# OpenEVSE_PLUS_v2.net
KiCad netlist of a schematic drawn in EAGLE
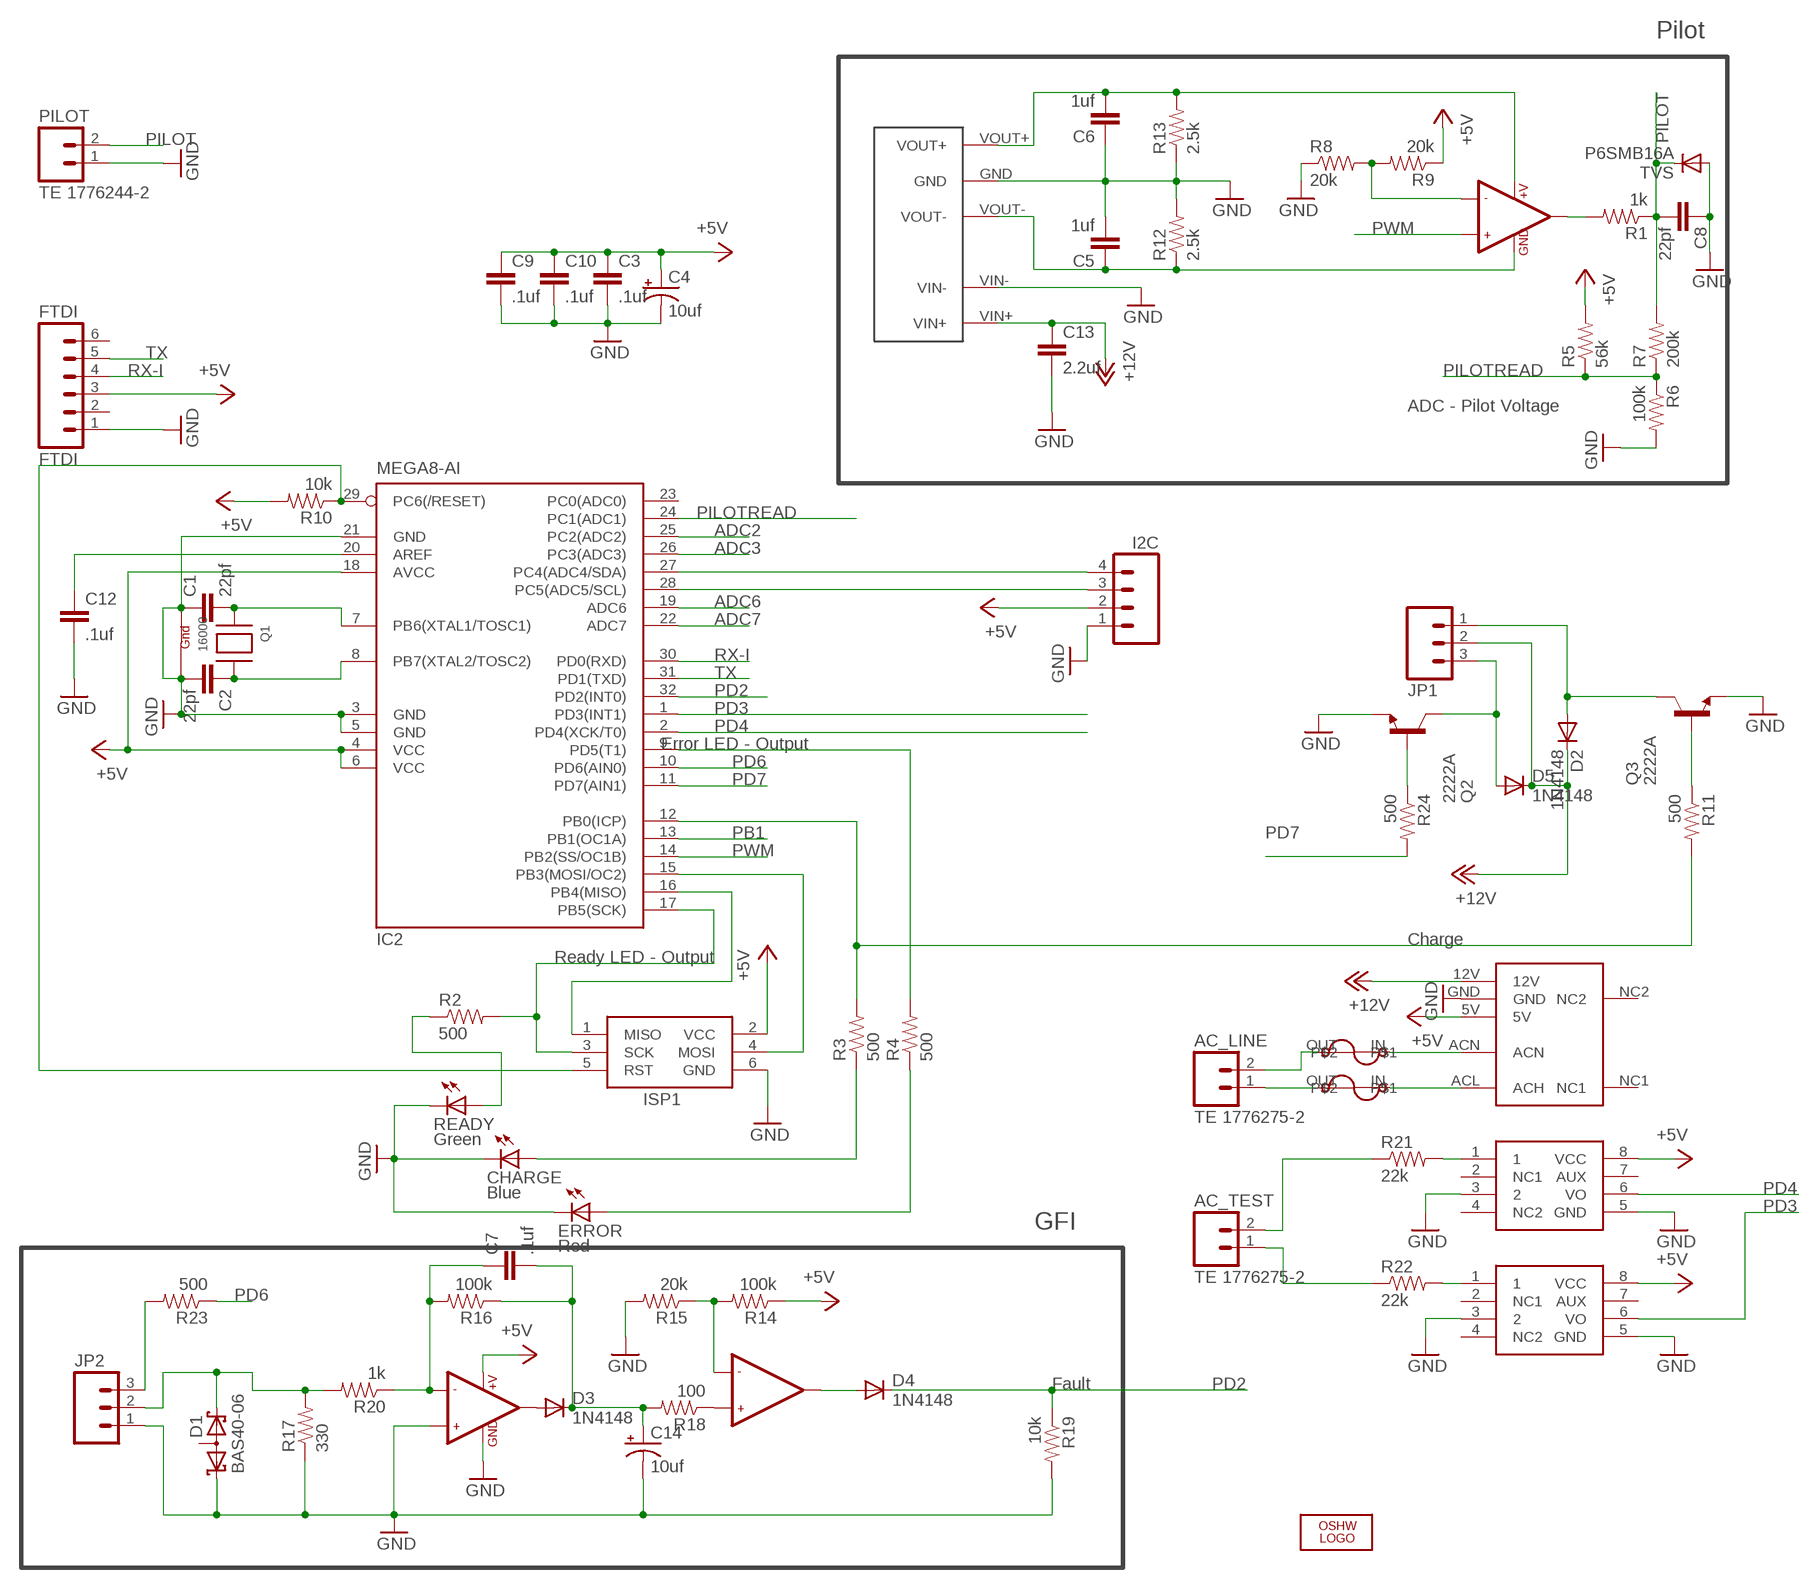
[diagram p0: schematic, sheet 1]

(export (version "E")
  (design (tool "Eeschema 10.0.6"))
  (components
    (comp (ref "AC_LINE")
      (value "TE 1776275-2")
      (footprint "eagle-import:SCREWTERMINAL-3.5MM-2_LOCK")
      (libsource (lib "eagle-import") (part "M023.5MM_LOCK"))
    )
    (comp (ref "AC_TEST")
      (value "TE 1776275-2")
      (footprint "eagle-import:SCREWTERMINAL-3.5MM-2_LOCK")
      (libsource (lib "eagle-import") (part "M023.5MM_LOCK"))
    )
    (comp (ref "C1")
      (value "22pf")
      (footprint "eagle-import:0805")
      (libsource (lib "eagle-import") (part "CAP0805"))
    )
    (comp (ref "C2")
      (value "22pf")
      (footprint "eagle-import:0805")
      (libsource (lib "eagle-import") (part "CAP0805"))
    )
    (comp (ref "C3")
      (value ".1uf")
      (footprint "eagle-import:0805")
      (libsource (lib "eagle-import") (part "CAP0805"))
    )
    (comp (ref "C4")
      (value "10uf")
      (footprint "eagle-import:EIA3216")
      (libsource (lib "eagle-import") (part "CAP_POL1206"))
    )
    (comp (ref "C5")
      (value "1uf")
      (footprint "eagle-import:0805")
      (libsource (lib "eagle-import") (part "CAP0805"))
    )
    (comp (ref "C6")
      (value "1uf")
      (footprint "eagle-import:0805")
      (libsource (lib "eagle-import") (part "CAP0805"))
    )
    (comp (ref "C7")
      (value ".1uf")
      (footprint "eagle-import:0805")
      (libsource (lib "eagle-import") (part "CAP0805"))
    )
    (comp (ref "C8")
      (value "22pf")
      (footprint "eagle-import:0805")
      (libsource (lib "eagle-import") (part "CAP0805"))
    )
    (comp (ref "C9")
      (value ".1uf")
      (footprint "eagle-import:0805")
      (libsource (lib "eagle-import") (part "CAP0805"))
    )
    (comp (ref "C10")
      (value ".1uf")
      (footprint "eagle-import:0805")
      (libsource (lib "eagle-import") (part "CAP0805"))
    )
    (comp (ref "C12")
      (value ".1uf")
      (footprint "eagle-import:0805")
      (libsource (lib "eagle-import") (part "CAP0805"))
    )
    (comp (ref "C13")
      (value "2.2uf")
      (footprint "eagle-import:0805")
      (libsource (lib "eagle-import") (part "CAP0805"))
    )
    (comp (ref "C14")
      (value "10uf")
      (footprint "eagle-import:EIA3216")
      (libsource (lib "eagle-import") (part "CAP_POL1206"))
    )
    (comp (ref "CHARGE")
      (value "Blue")
      (footprint "eagle-import:LED-0603")
      (libsource (lib "eagle-import") (part "LED0603"))
    )
    (comp (ref "D1")
      (value "BAS40-06")
      (footprint "eagle-import:SOT23")
      (libsource (lib "eagle-import") (part "BAS40-06"))
    )
    (comp (ref "D2")
      (value "1N4148")
      (footprint "eagle-import:SOD123")
      (libsource (lib "eagle-import") (part "DIODE-SOD123"))
    )
    (comp (ref "D3")
      (value "1N4148")
      (footprint "eagle-import:SOD123")
      (libsource (lib "eagle-import") (part "DIODE-SOD123"))
    )
    (comp (ref "D4")
      (value "1N4148")
      (footprint "eagle-import:SOD123")
      (libsource (lib "eagle-import") (part "DIODE-SOD123"))
    )
    (comp (ref "D5")
      (value "1N4148")
      (footprint "eagle-import:SOD123")
      (libsource (lib "eagle-import") (part "DIODE-SOD123"))
    )
    (comp (ref "DCDC")
      (value "D107E")
      (footprint "eagle-import:DCDC_SIP")
      (libsource (lib "eagle-import") (part "DCDC_SIP"))
    )
    (comp (ref "ERROR")
      (value "Red")
      (footprint "eagle-import:LED-0603")
      (libsource (lib "eagle-import") (part "LED0603"))
    )
    (comp (ref "FTDI")
      (value "FTDI")
      (footprint "eagle-import:1X06_LOCK")
      (libsource (lib "eagle-import") (part "M06LOCK"))
    )
    (comp (ref "I2C")
      (value "M04LOCK")
      (footprint "eagle-import:1X04_LOCK")
      (libsource (lib "eagle-import") (part "M04LOCK"))
    )
    (comp (ref "IC1")
      (value "MID400")
      (footprint "eagle-import:DIP08")
      (libsource (lib "eagle-import") (part "MID400"))
    )
    (comp (ref "IC2")
      (value "MEGA8-AI")
      (footprint "eagle-import:TQFP32-08")
      (fields (field (name "MPN") "ATMEGA8-16AU"))
      (libsource (lib "eagle-import") (part "MEGA8-AI"))
    )
    (comp (ref "IC3")
      (value "LMV358")
      (footprint "eagle-import:SO08")
      (libsource (lib "eagle-import") (part "LMV358"))
    )
    (comp (ref "IC4")
      (value "LMV358")
      (footprint "eagle-import:SO08")
      (libsource (lib "eagle-import") (part "LMV358"))
    )
    (comp (ref "IC5")
      (value "MID400")
      (footprint "eagle-import:DIP08")
      (libsource (lib "eagle-import") (part "MID400"))
    )
    (comp (ref "ISP1")
      (value "AVRISP-6")
      (footprint "eagle-import:AVRISP")
      (libsource (lib "eagle-import") (part "AVRISP-6"))
    )
    (comp (ref "JP1")
      (value "M03SCREW_LOCK")
      (footprint "eagle-import:SCREWTERMINAL-3.5MM-3_LOCK.007S")
      (libsource (lib "eagle-import") (part "M03SCREW_LOCK"))
    )
    (comp (ref "JP2")
      (value "M03LOCK")
      (footprint "eagle-import:1X03_LOCK")
      (libsource (lib "eagle-import") (part "M03LOCK"))
    )
    (comp (ref "LOGO1")
      (value "OSHW_LOGO_8MILX0150-NT")
      (footprint "eagle-import:OSHW_8X150_NOTEXT")
      (libsource (lib "eagle-import") (part "OSHW_LOGO_8MILX0150-NT"))
    )
    (comp (ref "PILOT")
      (value "TE 1776244-2")
      (footprint "eagle-import:SCREWTERMINAL-5MM-2")
      (libsource (lib "eagle-import") (part "M025MM"))
    )
    (comp (ref "Q1")
      (value "16000")
      (footprint "eagle-import:NX3225")
      (libsource (lib "eagle-import") (part "XTAL-4-3225"))
    )
    (comp (ref "Q2")
      (value "2222A")
      (footprint "eagle-import:SOT23")
      (libsource (lib "eagle-import") (part "BCX70SMD"))
    )
    (comp (ref "Q3")
      (value "2222A")
      (footprint "eagle-import:SOT23")
      (libsource (lib "eagle-import") (part "BCX70SMD"))
    )
    (comp (ref "R1")
      (value "1k")
      (footprint "eagle-import:0805")
      (libsource (lib "eagle-import") (part "RESISTOR0805-RES"))
    )
    (comp (ref "R2")
      (value "500")
      (footprint "eagle-import:0805")
      (libsource (lib "eagle-import") (part "RESISTOR0805-RES"))
    )
    (comp (ref "R3")
      (value "500")
      (footprint "eagle-import:0805")
      (libsource (lib "eagle-import") (part "RESISTOR0805-RES"))
    )
    (comp (ref "R4")
      (value "500")
      (footprint "eagle-import:0805")
      (libsource (lib "eagle-import") (part "RESISTOR0805-RES"))
    )
    (comp (ref "R5")
      (value "56k")
      (footprint "eagle-import:0805")
      (libsource (lib "eagle-import") (part "RESISTOR0805-RES"))
    )
    (comp (ref "R6")
      (value "100k")
      (footprint "eagle-import:0805")
      (libsource (lib "eagle-import") (part "RESISTOR0805-RES"))
    )
    (comp (ref "R7")
      (value "200k")
      (footprint "eagle-import:0805")
      (libsource (lib "eagle-import") (part "RESISTOR0805-RES"))
    )
    (comp (ref "R8")
      (value "20k")
      (footprint "eagle-import:0805")
      (libsource (lib "eagle-import") (part "RESISTOR0805-RES"))
    )
    (comp (ref "R9")
      (value "20k")
      (footprint "eagle-import:0805")
      (libsource (lib "eagle-import") (part "RESISTOR0805-RES"))
    )
    (comp (ref "R10")
      (value "10k")
      (footprint "eagle-import:0805")
      (libsource (lib "eagle-import") (part "RESISTOR0805-RES"))
    )
    (comp (ref "R11")
      (value "500")
      (footprint "eagle-import:0805")
      (libsource (lib "eagle-import") (part "RESISTOR0805-RES"))
    )
    (comp (ref "R12")
      (value "2.5k")
      (footprint "eagle-import:0805")
      (libsource (lib "eagle-import") (part "RESISTOR0805-RES"))
    )
    (comp (ref "R13")
      (value "2.5k")
      (footprint "eagle-import:0805")
      (libsource (lib "eagle-import") (part "RESISTOR0805-RES"))
    )
    (comp (ref "R14")
      (value "100k")
      (footprint "eagle-import:0805")
      (libsource (lib "eagle-import") (part "RESISTOR0805-RES"))
    )
    (comp (ref "R15")
      (value "20k")
      (footprint "eagle-import:0805")
      (libsource (lib "eagle-import") (part "RESISTOR0805-RES"))
    )
    (comp (ref "R16")
      (value "100k")
      (footprint "eagle-import:0805")
      (libsource (lib "eagle-import") (part "RESISTOR0805-RES"))
    )
    (comp (ref "R17")
      (value "330")
      (footprint "eagle-import:0805")
      (libsource (lib "eagle-import") (part "RESISTOR0805-RES"))
    )
    (comp (ref "R18")
      (value "100")
      (footprint "eagle-import:0805")
      (libsource (lib "eagle-import") (part "RESISTOR0805-RES"))
    )
    (comp (ref "R19")
      (value "10k")
      (footprint "eagle-import:0805")
      (libsource (lib "eagle-import") (part "RESISTOR0805-RES"))
    )
    (comp (ref "R20")
      (value "1k")
      (footprint "eagle-import:0805")
      (libsource (lib "eagle-import") (part "RESISTOR0805-RES"))
    )
    (comp (ref "R21")
      (value "22k")
      (footprint "eagle-import:AXIAL-0.4")
      (libsource (lib "eagle-import") (part "RESISTORPTH-1/4W"))
    )
    (comp (ref "R22")
      (value "22k")
      (footprint "eagle-import:AXIAL-0.4")
      (libsource (lib "eagle-import") (part "RESISTORPTH-1/4W"))
    )
    (comp (ref "R23")
      (value "500")
      (footprint "eagle-import:0805")
      (libsource (lib "eagle-import") (part "RESISTOR0805-RES"))
    )
    (comp (ref "R24")
      (value "500")
      (footprint "eagle-import:0805")
      (libsource (lib "eagle-import") (part "RESISTOR0805-RES"))
    )
    (comp (ref "READY")
      (value "Green")
      (footprint "eagle-import:LED-0603")
      (libsource (lib "eagle-import") (part "LED0603"))
    )
    (comp (ref "TVS")
      (value "P6SMB16A")
      (footprint "eagle-import:SMB")
      (libsource (lib "eagle-import") (part "DIODE-SMB"))
    )
    (comp (ref "U$1")
      (value "MPM-04E-1205")
      (footprint "eagle-import:MPM-04E-1205")
      (libsource (lib "eagle-import") (part "MPM-04E-1205"))
    )
    (comp (ref "U$2")
      (value "BEL1AFUSE")
      (footprint "eagle-import:BELFUSE1A")
      (libsource (lib "eagle-import") (part "BEL1AFUSE"))
    )
    (comp (ref "U$5")
      (value "BEL1AFUSE")
      (footprint "eagle-import:BELFUSE1A")
      (libsource (lib "eagle-import") (part "BEL1AFUSE"))
    )
  )
  (nets
    (net (code "1") (name "+5V") (class "Default")
      (node (ref "C10") (pin "1") (pinfunction "1_1") (pintype "passive"))
      (node (ref "C3") (pin "1") (pinfunction "1_1") (pintype "passive"))
      (node (ref "C4") (pin "A") (pinfunction "+_A") (pintype "passive"))
      (node (ref "C9") (pin "1") (pinfunction "1_1") (pintype "passive"))
      (node (ref "FTDI") (pin "3") (pinfunction "3_3") (pintype "passive"))
      (node (ref "I2C") (pin "2") (pinfunction "2_2") (pintype "passive"))
      (node (ref "IC1") (pin "8") (pinfunction "VCC_8") (pintype "bidirectional"))
      (node (ref "IC2") (pin "18") (pinfunction "AVCC_18") (pintype "power_in"))
      (node (ref "IC2") (pin "4") (pinfunction "VCC_4") (pintype "power_in"))
      (node (ref "IC2") (pin "6") (pinfunction "VCC_6") (pintype "power_in"))
      (node (ref "IC3") (pin "8") (pinfunction "+V_8") (pintype "power_in"))
      (node (ref "IC5") (pin "8") (pinfunction "VCC_8") (pintype "bidirectional"))
      (node (ref "ISP1") (pin "2") (pinfunction "VCC_2") (pintype "power_in"))
      (node (ref "R10") (pin "2") (pinfunction "2_2") (pintype "passive"))
      (node (ref "R14") (pin "1") (pinfunction "1_1") (pintype "passive"))
      (node (ref "R5") (pin "2") (pinfunction "2_2") (pintype "passive"))
      (node (ref "R9") (pin "1") (pinfunction "1_1") (pintype "passive"))
      (node (ref "U$1") (pin "5V") (pinfunction "5V_5V") (pintype "bidirectional"))
    )
    (net (code "2") (name "+12V") (class "Default")
      (node (ref "C13") (pin "1") (pinfunction "1_1") (pintype "passive"))
      (node (ref "D2") (pin "C") (pinfunction "C_C") (pintype "passive"))
      (node (ref "D5") (pin "C") (pinfunction "C_C") (pintype "passive"))
      (node (ref "DCDC") (pin "VIN+") (pinfunction "VIN+_VIN+") (pintype "bidirectional"))
      (node (ref "JP1") (pin "2") (pinfunction "2_2") (pintype "passive"))
      (node (ref "U$1") (pin "12V") (pinfunction "12V_12V") (pintype "bidirectional"))
    )
    (net (code "3") (name "/ADC2") (class "Default")
      (node (ref "IC2") (pin "25") (pinfunction "PC2(ADC2)_25") (pintype "bidirectional"))
    )
    (net (code "4") (name "/ADC3") (class "Default")
      (node (ref "IC2") (pin "26") (pinfunction "PC3(ADC3)_26") (pintype "bidirectional"))
    )
    (net (code "5") (name "/ADC6") (class "Default")
      (node (ref "IC2") (pin "19") (pinfunction "ADC6_19") (pintype "bidirectional"))
    )
    (net (code "6") (name "/ADC7") (class "Default")
      (node (ref "IC2") (pin "22") (pinfunction "ADC7_22") (pintype "bidirectional"))
    )
    (net (code "7") (name "/PB1") (class "Default")
      (node (ref "IC2") (pin "13") (pinfunction "PB1(OC1A)_13") (pintype "bidirectional"))
    )
    (net (code "8") (name "/PD2") (class "Default")
      (node (ref "D4") (pin "C") (pinfunction "C_C") (pintype "passive"))
      (node (ref "IC2") (pin "32") (pinfunction "PD2(INT0)_32") (pintype "bidirectional"))
      (node (ref "R19") (pin "1") (pinfunction "1_1") (pintype "passive"))
    )
    (net (code "9") (name "/PD3") (class "Default")
      (node (ref "IC2") (pin "1") (pinfunction "PD3(INT1)_1") (pintype "bidirectional"))
      (node (ref "IC5") (pin "6") (pinfunction "VO_6") (pintype "bidirectional"))
    )
    (net (code "10") (name "/PD4") (class "Default")
      (node (ref "IC1") (pin "6") (pinfunction "VO_6") (pintype "bidirectional"))
      (node (ref "IC2") (pin "2") (pinfunction "PD4(XCK/T0)_2") (pintype "bidirectional"))
    )
    (net (code "11") (name "/PD6") (class "Default")
      (node (ref "IC2") (pin "10") (pinfunction "PD6(AIN0)_10") (pintype "bidirectional"))
      (node (ref "R23") (pin "1") (pinfunction "1_1") (pintype "passive"))
    )
    (net (code "12") (name "/PD7") (class "Default")
      (node (ref "IC2") (pin "11") (pinfunction "PD7(AIN1)_11") (pintype "bidirectional"))
      (node (ref "R24") (pin "2") (pinfunction "2_2") (pintype "passive"))
    )
    (net (code "13") (name "/PILOT") (class "Default")
      (node (ref "C8") (pin "2") (pinfunction "2_2") (pintype "passive"))
      (node (ref "PILOT") (pin "2") (pinfunction "2_2") (pintype "passive"))
      (node (ref "R1") (pin "1") (pinfunction "1_1") (pintype "passive"))
      (node (ref "R7") (pin "2") (pinfunction "2_2") (pintype "passive"))
      (node (ref "TVS") (pin "C") (pinfunction "C_C") (pintype "passive"))
    )
    (net (code "14") (name "/PILOTREAD") (class "Default")
      (node (ref "IC2") (pin "24") (pinfunction "PC1(ADC1)_24") (pintype "bidirectional"))
      (node (ref "R5") (pin "1") (pinfunction "1_1") (pintype "passive"))
      (node (ref "R6") (pin "1") (pinfunction "1_1") (pintype "passive"))
      (node (ref "R7") (pin "1") (pinfunction "1_1") (pintype "passive"))
    )
    (net (code "15") (name "/PWM") (class "Default")
      (node (ref "IC2") (pin "14") (pinfunction "PB2(SS/OC1B)_14") (pintype "bidirectional"))
      (node (ref "IC4") (pin "3") (pinfunction "+IN1_3") (pintype "input"))
    )
    (net (code "16") (name "/RX-I") (class "Default")
      (node (ref "FTDI") (pin "4") (pinfunction "4_4") (pintype "passive"))
      (node (ref "IC2") (pin "30") (pinfunction "PD0(RXD)_30") (pintype "bidirectional"))
    )
    (net (code "17") (name "/TX") (class "Default")
      (node (ref "FTDI") (pin "5") (pinfunction "5_5") (pintype "passive"))
      (node (ref "IC2") (pin "31") (pinfunction "PD1(TXD)_31") (pintype "bidirectional"))
    )
    (net (code "18") (name "GND") (class "Default")
      (node (ref "C1") (pin "1") (pinfunction "1_1") (pintype "passive"))
      (node (ref "C10") (pin "2") (pinfunction "2_2") (pintype "passive"))
      (node (ref "C12") (pin "2") (pinfunction "2_2") (pintype "passive"))
      (node (ref "C13") (pin "2") (pinfunction "2_2") (pintype "passive"))
      (node (ref "C14") (pin "C") (pinfunction "-_C") (pintype "passive"))
      (node (ref "C2") (pin "2") (pinfunction "2_2") (pintype "passive"))
      (node (ref "C3") (pin "2") (pinfunction "2_2") (pintype "passive"))
      (node (ref "C4") (pin "C") (pinfunction "-_C") (pintype "passive"))
      (node (ref "C5") (pin "2") (pinfunction "2_2") (pintype "passive"))
      (node (ref "C6") (pin "1") (pinfunction "1_1") (pintype "passive"))
      (node (ref "C8") (pin "1") (pinfunction "1_1") (pintype "passive"))
      (node (ref "C9") (pin "2") (pinfunction "2_2") (pintype "passive"))
      (node (ref "CHARGE") (pin "C") (pinfunction "C_C") (pintype "passive"))
      (node (ref "D1") (pin "1") (pinfunction "K1_1") (pintype "passive"))
      (node (ref "DCDC") (pin "GND") (pinfunction "GND_GND") (pintype "bidirectional"))
      (node (ref "DCDC") (pin "VIN-") (pinfunction "VIN-_VIN-") (pintype "bidirectional"))
      (node (ref "ERROR") (pin "C") (pinfunction "C_C") (pintype "passive"))
      (node (ref "FTDI") (pin "1") (pinfunction "1_1") (pintype "passive"))
      (node (ref "I2C") (pin "1") (pinfunction "1_1") (pintype "passive"))
      (node (ref "IC1") (pin "3") (pinfunction "2_3") (pintype "bidirectional"))
      (node (ref "IC1") (pin "5") (pinfunction "GND_5") (pintype "bidirectional"))
      (node (ref "IC2") (pin "21") (pinfunction "GND_21") (pintype "power_in"))
      (node (ref "IC2") (pin "3") (pinfunction "GND_3") (pintype "power_in"))
      (node (ref "IC2") (pin "5") (pinfunction "GND_5") (pintype "power_in"))
      (node (ref "IC3") (pin "3") (pinfunction "+IN1_3") (pintype "input"))
      (node (ref "IC3") (pin "4") (pinfunction "GND_4") (pintype "power_in"))
      (node (ref "IC5") (pin "3") (pinfunction "2_3") (pintype "bidirectional"))
      (node (ref "IC5") (pin "5") (pinfunction "GND_5") (pintype "bidirectional"))
      (node (ref "ISP1") (pin "6") (pinfunction "GND_6") (pintype "power_in"))
      (node (ref "JP2") (pin "1") (pinfunction "1_1") (pintype "passive"))
      (node (ref "PILOT") (pin "1") (pinfunction "1_1") (pintype "passive"))
      (node (ref "Q1") (pin "1") (pinfunction "G1_1") (pintype "power_in"))
      (node (ref "Q1") (pin "3") (pinfunction "G2_3") (pintype "power_in"))
      (node (ref "Q2") (pin "2") (pinfunction "E_2") (pintype "passive"))
      (node (ref "Q3") (pin "2") (pinfunction "E_2") (pintype "passive"))
      (node (ref "R12") (pin "2") (pinfunction "2_2") (pintype "passive"))
      (node (ref "R13") (pin "1") (pinfunction "1_1") (pintype "passive"))
      (node (ref "R15") (pin "2") (pinfunction "2_2") (pintype "passive"))
      (node (ref "R17") (pin "1") (pinfunction "1_1") (pintype "passive"))
      (node (ref "R19") (pin "2") (pinfunction "2_2") (pintype "passive"))
      (node (ref "R6") (pin "2") (pinfunction "2_2") (pintype "passive"))
      (node (ref "R8") (pin "1") (pinfunction "1_1") (pintype "passive"))
      (node (ref "READY") (pin "C") (pinfunction "C_C") (pintype "passive"))
      (node (ref "TVS") (pin "A") (pinfunction "A_A") (pintype "passive"))
      (node (ref "U$1") (pin "GND") (pinfunction "GND_GND") (pintype "bidirectional"))
    )
    (net (code "19") (name "Net-(C14-+)") (class "Default")
      (node (ref "C14") (pin "A") (pinfunction "+_A") (pintype "passive"))
      (node (ref "C7") (pin "2") (pinfunction "2_2") (pintype "passive"))
      (node (ref "D3") (pin "C") (pinfunction "C_C") (pintype "passive"))
      (node (ref "R16") (pin "1") (pinfunction "1_1") (pintype "passive"))
      (node (ref "R18") (pin "2") (pinfunction "2_2") (pintype "passive"))
    )
    (net (code "20") (name "Net-(CHARGE-PadA)") (class "Default")
      (node (ref "CHARGE") (pin "A") (pinfunction "A_A") (pintype "passive"))
      (node (ref "R3") (pin "1") (pinfunction "1_1") (pintype "passive"))
    )
    (net (code "21") (name "Net-(D1-K2)") (class "Default")
      (node (ref "D1") (pin "2") (pinfunction "K2_2") (pintype "passive"))
      (node (ref "JP2") (pin "2") (pinfunction "2_2") (pintype "passive"))
      (node (ref "R17") (pin "2") (pinfunction "2_2") (pintype "passive"))
      (node (ref "R20") (pin "2") (pinfunction "2_2") (pintype "passive"))
    )
    (net (code "22") (name "Net-(ERROR-PadA)") (class "Default")
      (node (ref "ERROR") (pin "A") (pinfunction "A_A") (pintype "passive"))
      (node (ref "R4") (pin "1") (pinfunction "1_1") (pintype "passive"))
    )
    (net (code "23") (name "Net-(IC2-AREF)") (class "Default")
      (node (ref "C12") (pin "1") (pinfunction "1_1") (pintype "passive"))
      (node (ref "IC2") (pin "20") (pinfunction "AREF_20") (pintype "passive"))
    )
    (net (code "24") (name "Net-(IC2-PB0(ICP))") (class "Default")
      (node (ref "IC2") (pin "12") (pinfunction "PB0(ICP)_12") (pintype "bidirectional"))
      (node (ref "R11") (pin "2") (pinfunction "2_2") (pintype "passive"))
      (node (ref "R3") (pin "2") (pinfunction "2_2") (pintype "passive"))
    )
    (net (code "25") (name "Net-(IC2-PB3(MOSI{slash}OC2))") (class "Default")
      (node (ref "IC2") (pin "15") (pinfunction "PB3(MOSI/OC2)_15") (pintype "bidirectional"))
      (node (ref "ISP1") (pin "4") (pinfunction "MOSI_4") (pintype "output"))
    )
    (net (code "26") (name "Net-(IC2-PB4(MISO))") (class "Default")
      (node (ref "IC2") (pin "16") (pinfunction "PB4(MISO)_16") (pintype "bidirectional"))
      (node (ref "ISP1") (pin "1") (pinfunction "MISO_1") (pintype "input"))
    )
    (net (code "27") (name "Net-(IC2-PB5(SCK))") (class "Default")
      (node (ref "IC2") (pin "17") (pinfunction "PB5(SCK)_17") (pintype "bidirectional"))
      (node (ref "ISP1") (pin "3") (pinfunction "SCK_3") (pintype "output"))
      (node (ref "R2") (pin "2") (pinfunction "2_2") (pintype "passive"))
    )
    (net (code "28") (name "Net-(IC2-PB6(XTAL1{slash}TOSC1))") (class "Default")
      (node (ref "C1") (pin "2") (pinfunction "2_2") (pintype "passive"))
      (node (ref "IC2") (pin "7") (pinfunction "PB6(XTAL1/TOSC1)_7") (pintype "bidirectional"))
      (node (ref "Q1") (pin "2") (pinfunction "X1_2") (pintype "bidirectional"))
    )
    (net (code "29") (name "Net-(IC2-PB7(XTAL2{slash}TOSC2))") (class "Default")
      (node (ref "C2") (pin "1") (pinfunction "1_1") (pintype "passive"))
      (node (ref "IC2") (pin "8") (pinfunction "PB7(XTAL2/TOSC2)_8") (pintype "bidirectional"))
      (node (ref "Q1") (pin "4") (pinfunction "X2_4") (pintype "bidirectional"))
    )
    (net (code "30") (name "Net-(IC2-PC4(ADC4{slash}SDA))") (class "Default")
      (node (ref "I2C") (pin "4") (pinfunction "4_4") (pintype "passive"))
      (node (ref "IC2") (pin "27") (pinfunction "PC4(ADC4/SDA)_27") (pintype "bidirectional"))
    )
    (net (code "31") (name "Net-(IC2-PC5(ADC5{slash}SCL))") (class "Default")
      (node (ref "I2C") (pin "3") (pinfunction "3_3") (pintype "passive"))
      (node (ref "IC2") (pin "28") (pinfunction "PC5(ADC5/SCL)_28") (pintype "bidirectional"))
    )
    (net (code "32") (name "Net-(IC2-PC6({slash}RESET))") (class "Default")
      (node (ref "IC2") (pin "29") (pinfunction "PC6(/RESET)_29") (pintype "bidirectional"))
      (node (ref "ISP1") (pin "5") (pinfunction "RST_5") (pintype "output"))
      (node (ref "R10") (pin "1") (pinfunction "1_1") (pintype "passive"))
    )
    (net (code "33") (name "Net-(IC2-PD5(T1))") (class "Default")
      (node (ref "IC2") (pin "9") (pinfunction "PD5(T1)_9") (pintype "bidirectional"))
      (node (ref "R4") (pin "2") (pinfunction "2_2") (pintype "passive"))
    )
    (net (code "34") (name "Net-(IC3A--IN1)") (class "Default")
      (node (ref "C7") (pin "1") (pinfunction "1_1") (pintype "passive"))
      (node (ref "IC3") (pin "2") (pinfunction "-IN1_2") (pintype "input"))
      (node (ref "R16") (pin "2") (pinfunction "2_2") (pintype "passive"))
      (node (ref "R20") (pin "1") (pinfunction "1_1") (pintype "passive"))
    )
    (net (code "35") (name "Net-(IC3A-OUT1)") (class "Default")
      (node (ref "D3") (pin "A") (pinfunction "A_A") (pintype "passive"))
      (node (ref "IC3") (pin "1") (pinfunction "OUT1_1") (pintype "output"))
    )
    (net (code "36") (name "Net-(IC3B-+IN2)") (class "Default")
      (node (ref "IC3") (pin "5") (pinfunction "+IN2_5") (pintype "input"))
      (node (ref "R18") (pin "1") (pinfunction "1_1") (pintype "passive"))
    )
    (net (code "37") (name "Net-(IC3B--IN2)") (class "Default")
      (node (ref "IC3") (pin "6") (pinfunction "-IN2_6") (pintype "input"))
      (node (ref "R14") (pin "2") (pinfunction "2_2") (pintype "passive"))
      (node (ref "R15") (pin "1") (pinfunction "1_1") (pintype "passive"))
    )
    (net (code "38") (name "Net-(IC3B-OUT2)") (class "Default")
      (node (ref "D4") (pin "A") (pinfunction "A_A") (pintype "passive"))
      (node (ref "IC3") (pin "7") (pinfunction "OUT2_7") (pintype "output"))
    )
    (net (code "39") (name "Net-(IC4A-+V)") (class "Default")
      (node (ref "C6") (pin "2") (pinfunction "2_2") (pintype "passive"))
      (node (ref "DCDC") (pin "VOUT+") (pinfunction "VOUT+_VOUT+") (pintype "bidirectional"))
      (node (ref "IC4") (pin "8") (pinfunction "+V_8") (pintype "power_in"))
      (node (ref "R13") (pin "2") (pinfunction "2_2") (pintype "passive"))
    )
    (net (code "40") (name "Net-(IC4A--IN1)") (class "Default")
      (node (ref "IC4") (pin "2") (pinfunction "-IN1_2") (pintype "input"))
      (node (ref "R8") (pin "2") (pinfunction "2_2") (pintype "passive"))
      (node (ref "R9") (pin "2") (pinfunction "2_2") (pintype "passive"))
    )
    (net (code "41") (name "Net-(IC4A-GND)") (class "Default")
      (node (ref "C5") (pin "1") (pinfunction "1_1") (pintype "passive"))
      (node (ref "DCDC") (pin "VOUT-") (pinfunction "VOUT-_VOUT-") (pintype "bidirectional"))
      (node (ref "IC4") (pin "4") (pinfunction "GND_4") (pintype "power_in"))
      (node (ref "R12") (pin "1") (pinfunction "1_1") (pintype "passive"))
    )
    (net (code "42") (name "Net-(IC4A-OUT1)") (class "Default")
      (node (ref "IC4") (pin "1") (pinfunction "OUT1_1") (pintype "output"))
      (node (ref "R1") (pin "2") (pinfunction "2_2") (pintype "passive"))
    )
    (net (code "43") (name "Net-(JP2-Pad3)") (class "Default")
      (node (ref "JP2") (pin "3") (pinfunction "3_3") (pintype "passive"))
      (node (ref "R23") (pin "2") (pinfunction "2_2") (pintype "passive"))
    )
    (net (code "44") (name "Net-(Q2-B)") (class "Default")
      (node (ref "Q2") (pin "1") (pinfunction "B_1") (pintype "passive"))
      (node (ref "R24") (pin "1") (pinfunction "1_1") (pintype "passive"))
    )
    (net (code "45") (name "Net-(Q2-C)") (class "Default")
      (node (ref "D5") (pin "A") (pinfunction "A_A") (pintype "passive"))
      (node (ref "JP1") (pin "3") (pinfunction "3_3") (pintype "passive"))
      (node (ref "Q2") (pin "3") (pinfunction "C_3") (pintype "passive"))
    )
    (net (code "46") (name "Net-(Q3-B)") (class "Default")
      (node (ref "Q3") (pin "1") (pinfunction "B_1") (pintype "passive"))
      (node (ref "R11") (pin "1") (pinfunction "1_1") (pintype "passive"))
    )
    (net (code "47") (name "Net-(Q3-C)") (class "Default")
      (node (ref "D2") (pin "A") (pinfunction "A_A") (pintype "passive"))
      (node (ref "JP1") (pin "1") (pinfunction "1_1") (pintype "passive"))
      (node (ref "Q3") (pin "3") (pinfunction "C_3") (pintype "passive"))
    )
    (net (code "48") (name "Net-(R2-Pad1)") (class "Default")
      (node (ref "R2") (pin "1") (pinfunction "1_1") (pintype "passive"))
      (node (ref "READY") (pin "A") (pinfunction "A_A") (pintype "passive"))
    )
    (net (code "49") (name "Net-(R21-1)") (class "Default")
      (node (ref "AC_TEST") (pin "2") (pinfunction "2_2") (pintype "passive"))
      (node (ref "R21") (pin "P$1") (pinfunction "1_P$1") (pintype "passive"))
    )
    (net (code "50") (name "Net-(R21-2)") (class "Default")
      (node (ref "IC1") (pin "1") (pinfunction "1_1") (pintype "bidirectional"))
      (node (ref "R21") (pin "P$2") (pinfunction "2_P$2") (pintype "passive"))
    )
    (net (code "51") (name "Net-(R22-1)") (class "Default")
      (node (ref "AC_TEST") (pin "1") (pinfunction "1_1") (pintype "passive"))
      (node (ref "R22") (pin "P$1") (pinfunction "1_P$1") (pintype "passive"))
    )
    (net (code "52") (name "Net-(R22-2)") (class "Default")
      (node (ref "IC5") (pin "1") (pinfunction "1_1") (pintype "bidirectional"))
      (node (ref "R22") (pin "P$2") (pinfunction "2_P$2") (pintype "passive"))
    )
    (net (code "53") (name "Net-(U$1-ACH)") (class "Default")
      (node (ref "U$1") (pin "ACL") (pinfunction "ACH_ACL") (pintype "bidirectional"))
      (node (ref "U$2") (pin "IN") (pinfunction "P$2_IN") (pintype "bidirectional"))
    )
    (net (code "54") (name "Net-(U$2-P$1)") (class "Default")
      (node (ref "AC_LINE") (pin "1") (pinfunction "1_1") (pintype "passive"))
      (node (ref "U$2") (pin "OUT") (pinfunction "P$1_OUT") (pintype "bidirectional"))
    )
    (net (code "55") (name "Net-(U$5-P$1)") (class "Default")
      (node (ref "AC_LINE") (pin "2") (pinfunction "2_2") (pintype "passive"))
      (node (ref "U$5") (pin "OUT") (pinfunction "P$1_OUT") (pintype "bidirectional"))
    )
    (net (code "56") (name "Net-(U$5-P$2)") (class "Default")
      (node (ref "U$1") (pin "ACN") (pinfunction "ACN_ACN") (pintype "bidirectional"))
      (node (ref "U$5") (pin "IN") (pinfunction "P$2_IN") (pintype "bidirectional"))
    )
    (net (code "57") (name "unconnected-(D1-AA-Pad3)") (class "Default")
      (node (ref "D1") (pin "3") (pinfunction "AA_3") (pintype "passive"))
    )
    (net (code "58") (name "unconnected-(FTDI-Pad2)") (class "Default")
      (node (ref "FTDI") (pin "2") (pinfunction "2_2") (pintype "passive"))
    )
    (net (code "59") (name "unconnected-(FTDI-Pad6)") (class "Default")
      (node (ref "FTDI") (pin "6") (pinfunction "6_6") (pintype "passive"))
    )
    (net (code "60") (name "unconnected-(IC1-AUX-Pad7)") (class "Default")
      (node (ref "IC1") (pin "7") (pinfunction "AUX_7") (pintype "bidirectional"))
    )
    (net (code "61") (name "unconnected-(IC1-NC1-Pad2)") (class "Default")
      (node (ref "IC1") (pin "2") (pinfunction "NC1_2") (pintype "bidirectional"))
    )
    (net (code "62") (name "unconnected-(IC1-NC2-Pad4)") (class "Default")
      (node (ref "IC1") (pin "4") (pinfunction "NC2_4") (pintype "bidirectional"))
    )
    (net (code "63") (name "unconnected-(IC2-PC0(ADC0)-Pad23)") (class "Default")
      (node (ref "IC2") (pin "23") (pinfunction "PC0(ADC0)_23") (pintype "bidirectional"))
    )
    (net (code "64") (name "unconnected-(IC5-AUX-Pad7)") (class "Default")
      (node (ref "IC5") (pin "7") (pinfunction "AUX_7") (pintype "bidirectional"))
    )
    (net (code "65") (name "unconnected-(IC5-NC1-Pad2)") (class "Default")
      (node (ref "IC5") (pin "2") (pinfunction "NC1_2") (pintype "bidirectional"))
    )
    (net (code "66") (name "unconnected-(IC5-NC2-Pad4)") (class "Default")
      (node (ref "IC5") (pin "4") (pinfunction "NC2_4") (pintype "bidirectional"))
    )
    (net (code "67") (name "unconnected-(U$1-PadNC1)") (class "Default")
      (node (ref "U$1") (pin "NC1") (pinfunction "NC1_NC1") (pintype "bidirectional"))
    )
    (net (code "68") (name "unconnected-(U$1-PadNC2)") (class "Default")
      (node (ref "U$1") (pin "NC2") (pinfunction "NC2_NC2") (pintype "bidirectional"))
    )
  )
)
